# PATHOS_SOM_IO.net
KiCad netlist of a schematic drawn in Altium Designer
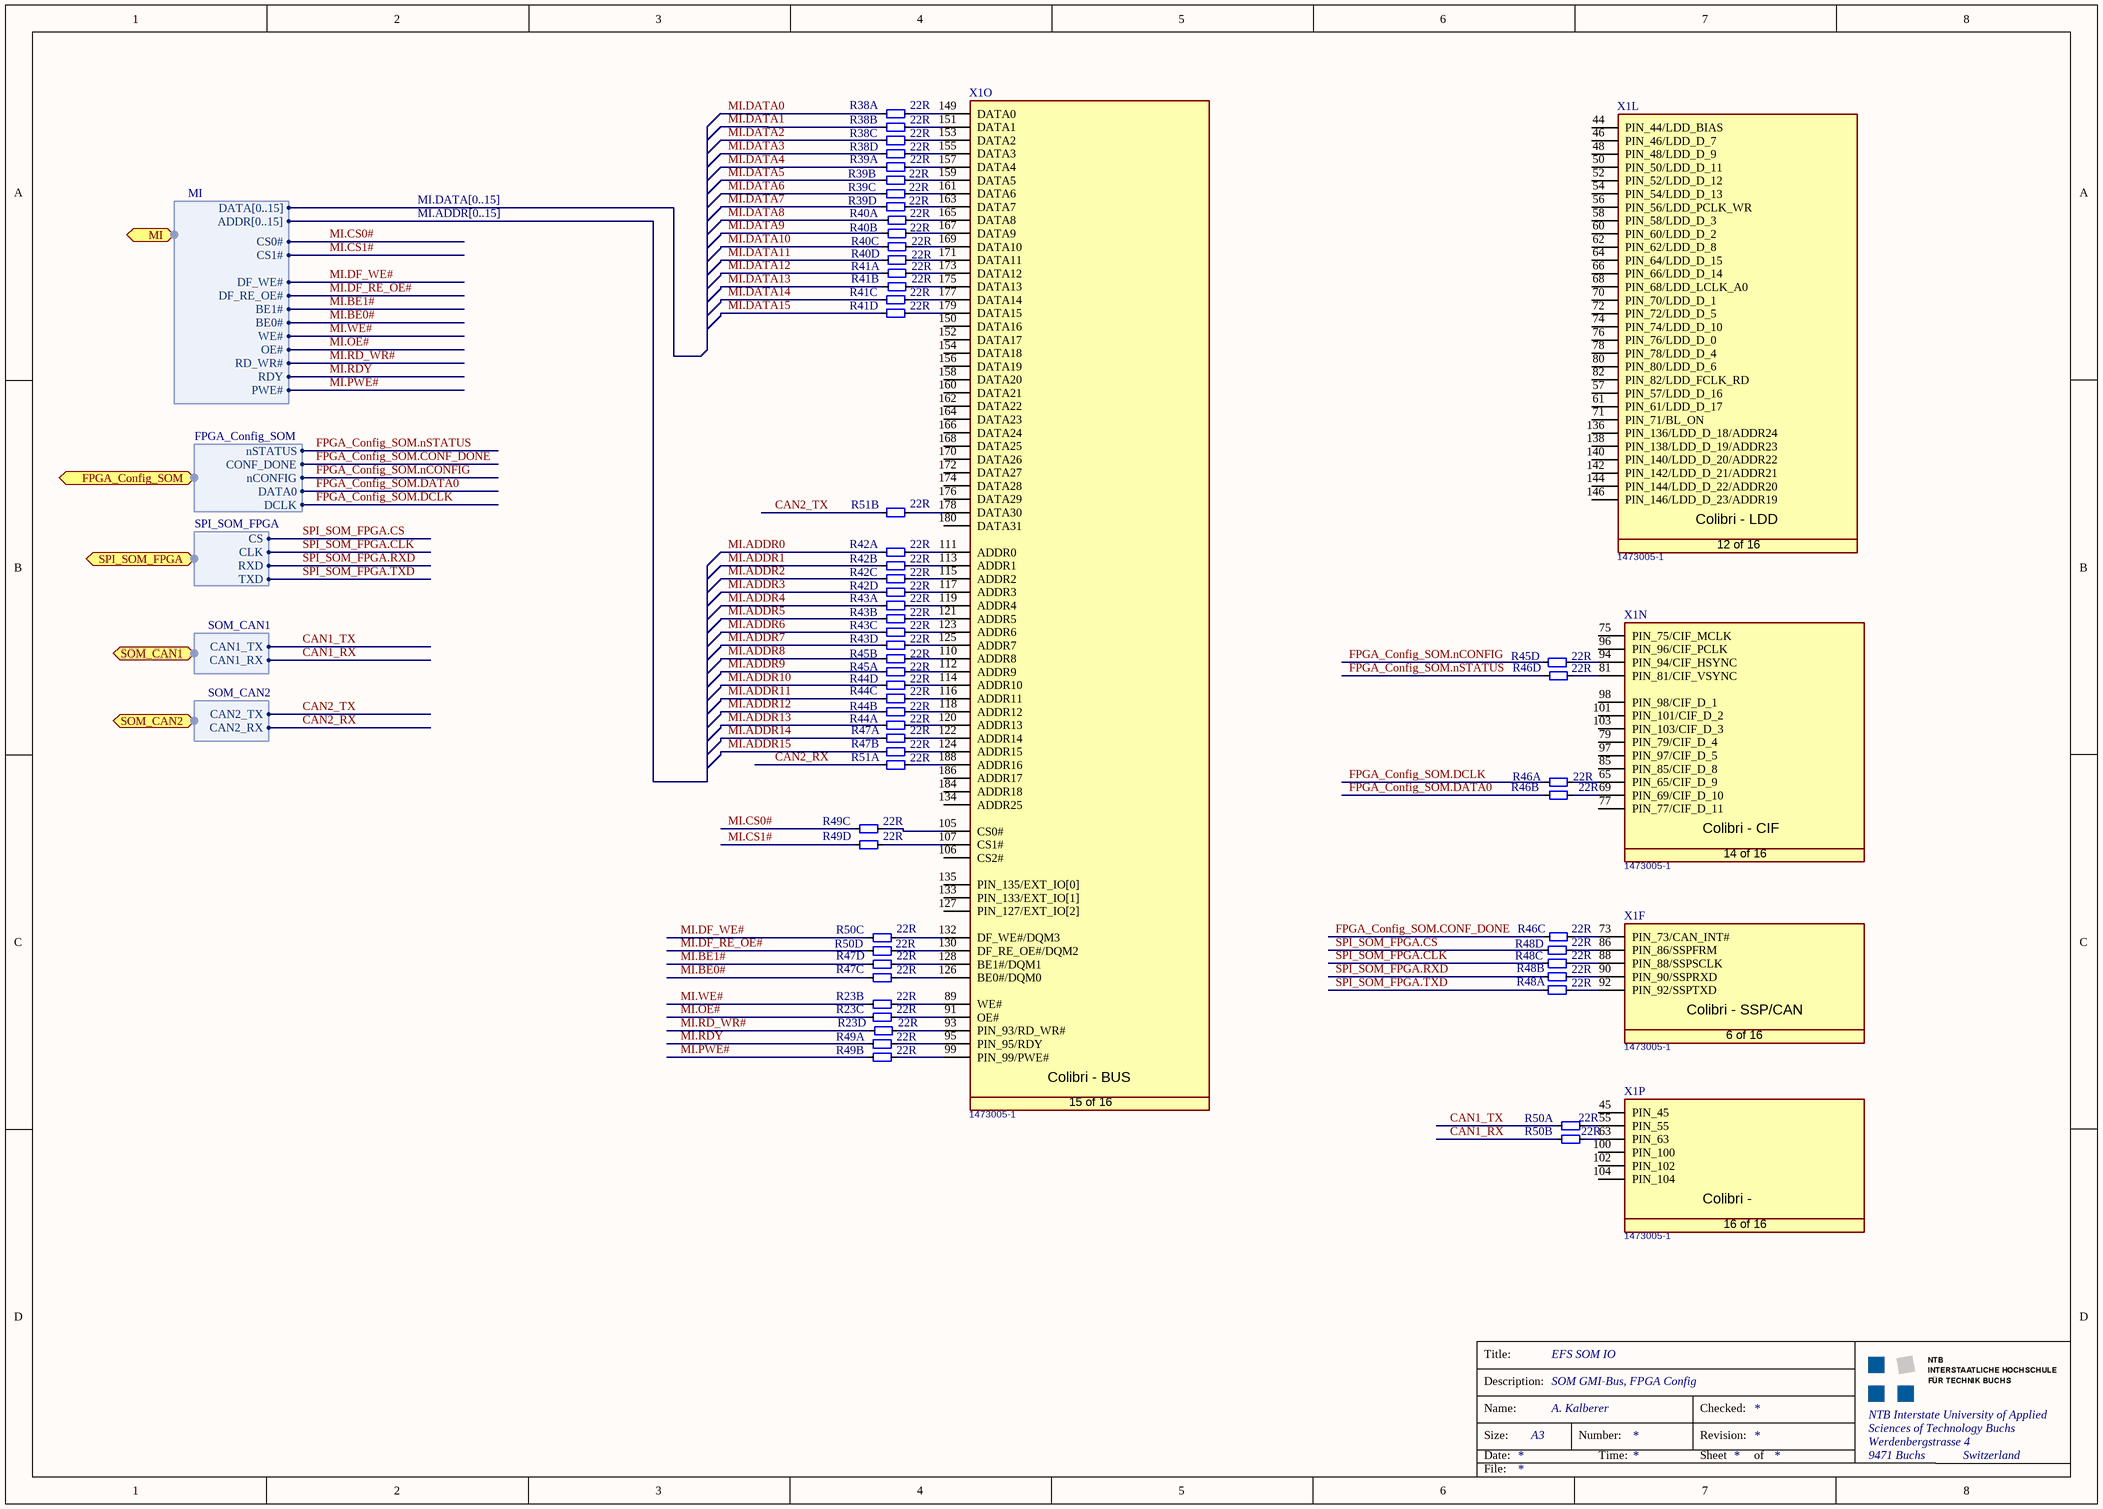
[diagram p0: PATHOS_SOM_IO.SchDoc]

(export (version "E")
  (design (tool "Eeschema 10.0.6"))
  (components
    (comp (ref "R23")
      (value "22R")
      (footprint "R_Array_CAT16-J4")
      (fields (field (name "Comment") "R Array"))
      (libsource (lib "EFSSensorboard_1") (part "R_Array"))
    )
    (comp (ref "R38")
      (value "22R")
      (footprint "R_Array_CAT16-J4")
      (fields (field (name "Comment") "R Array"))
      (libsource (lib "EFSSensorboard_1") (part "R_Array"))
    )
    (comp (ref "R39")
      (value "22R")
      (footprint "R_Array_CAT16-J4")
      (fields (field (name "Comment") "R Array"))
      (libsource (lib "EFSSensorboard_1") (part "R_Array"))
    )
    (comp (ref "R40")
      (value "22R")
      (footprint "R_Array_CAT16-J4")
      (fields (field (name "Comment") "R Array"))
      (libsource (lib "EFSSensorboard_1") (part "R_Array"))
    )
    (comp (ref "R41")
      (value "22R")
      (footprint "R_Array_CAT16-J4")
      (fields (field (name "Comment") "R Array"))
      (libsource (lib "EFSSensorboard_1") (part "R_Array"))
    )
    (comp (ref "R42")
      (value "22R")
      (footprint "R_Array_CAT16-J4")
      (fields (field (name "Comment") "R Array"))
      (libsource (lib "EFSSensorboard_1") (part "R_Array"))
    )
    (comp (ref "R43")
      (value "22R")
      (footprint "R_Array_CAT16-J4")
      (fields (field (name "Comment") "R Array"))
      (libsource (lib "EFSSensorboard_1") (part "R_Array"))
    )
    (comp (ref "R44")
      (value "22R")
      (footprint "R_Array_CAT16-J4")
      (fields (field (name "Comment") "R Array"))
      (libsource (lib "EFSSensorboard_1") (part "R_Array"))
    )
    (comp (ref "R45")
      (value "22R")
      (footprint "R_Array_CAT16-J4")
      (fields (field (name "Comment") "R Array"))
      (libsource (lib "EFSSensorboard_1") (part "R_Array"))
    )
    (comp (ref "R46")
      (value "22R")
      (footprint "R_Array_CAT16-J4")
      (fields (field (name "Comment") "R Array"))
      (libsource (lib "EFSSensorboard_1") (part "R_Array"))
    )
    (comp (ref "R47")
      (value "22R")
      (footprint "R_Array_CAT16-J4")
      (fields (field (name "Comment") "R Array"))
      (libsource (lib "EFS_Sensorboard") (part "R_Array"))
    )
    (comp (ref "R48")
      (value "22R")
      (footprint "R_Array_CAT16-J4")
      (fields (field (name "Comment") "R Array"))
      (libsource (lib "EFSSensorboard_1") (part "R_Array"))
    )
    (comp (ref "R49")
      (value "22R")
      (footprint "R_Array_CAT16-J4")
      (fields (field (name "Comment") "R Array"))
      (libsource (lib "EFSSensorboard_1") (part "R_Array"))
    )
    (comp (ref "R50")
      (value "22R")
      (footprint "R_Array_CAT16-J4")
      (fields (field (name "Comment") "R Array"))
      (libsource (lib "EFSSensorboard_1") (part "R_Array"))
    )
    (comp (ref "R51")
      (value "22R")
      (footprint "R_Array_CAT16-J4")
      (fields (field (name "Comment") "R Array"))
      (libsource (lib "EFS_Sensorboard") (part "R_Array"))
    )
    (comp (ref "X1")
      (value "CON-Tyco-1473005-1-200-0.6mm")
      (footprint "T_Tyco_1473005-1")
      (description "SODIMM Connector")
      (fields (field (name "MANUFACTURER PART NO.") "1473005-1"))
      (libsource (lib "EFS_Sensorboard") (part "CON-Tyco-1473005-1-200-0.6mm"))
    )
  )
  (nets
    (net (code "6") (name "/CAN1_RX") (class "Default")
      (node (ref "R50") (pin "2B") (pinfunction "2_2B") (pintype "passive"))
    )
    (net (code "7") (name "/CAN1_TX") (class "Default")
      (node (ref "R50") (pin "2A") (pinfunction "2_2A") (pintype "passive"))
    )
    (net (code "8") (name "/CAN2_RX") (class "Default")
      (node (ref "R51") (pin "1A") (pinfunction "1_1A") (pintype "passive"))
    )
    (net (code "9") (name "/CAN2_TX") (class "Default")
      (node (ref "R51") (pin "1B") (pinfunction "1_1B") (pintype "passive"))
    )
    (net (code "10") (name "/FPGA_Config_SOM.CONF_DONE") (class "Default")
      (node (ref "R46") (pin "1C") (pinfunction "1_1C") (pintype "passive"))
    )
    (net (code "11") (name "/FPGA_Config_SOM.DATA0") (class "Default")
      (node (ref "R46") (pin "1B") (pinfunction "1_1B") (pintype "passive"))
    )
    (net (code "12") (name "/FPGA_Config_SOM.DCLK") (class "Default")
      (node (ref "R46") (pin "1A") (pinfunction "1_1A") (pintype "passive"))
    )
    (net (code "13") (name "/FPGA_Config_SOM.nCONFIG") (class "Default")
      (node (ref "R45") (pin "1D") (pinfunction "1_1D") (pintype "passive"))
    )
    (net (code "14") (name "/FPGA_Config_SOM.nSTATUS") (class "Default")
      (node (ref "R46") (pin "1D") (pinfunction "1_1D") (pintype "passive"))
    )
    (net (code "15") (name "/MI.ADDR0") (class "Default")
      (node (ref "R42") (pin "1A") (pinfunction "1_1A") (pintype "passive"))
    )
    (net (code "16") (name "/MI.ADDR1") (class "Default")
      (node (ref "R42") (pin "1B") (pinfunction "1_1B") (pintype "passive"))
    )
    (net (code "17") (name "/MI.ADDR2") (class "Default")
      (node (ref "R42") (pin "1C") (pinfunction "1_1C") (pintype "passive"))
    )
    (net (code "18") (name "/MI.ADDR3") (class "Default")
      (node (ref "R42") (pin "1D") (pinfunction "1_1D") (pintype "passive"))
    )
    (net (code "19") (name "/MI.ADDR4") (class "Default")
      (node (ref "R43") (pin "1A") (pinfunction "1_1A") (pintype "passive"))
    )
    (net (code "20") (name "/MI.ADDR5") (class "Default")
      (node (ref "R43") (pin "1B") (pinfunction "1_1B") (pintype "passive"))
    )
    (net (code "21") (name "/MI.ADDR6") (class "Default")
      (node (ref "R43") (pin "1C") (pinfunction "1_1C") (pintype "passive"))
    )
    (net (code "22") (name "/MI.ADDR7") (class "Default")
      (node (ref "R43") (pin "1D") (pinfunction "1_1D") (pintype "passive"))
    )
    (net (code "23") (name "/MI.ADDR8") (class "Default")
      (node (ref "R45") (pin "1B") (pinfunction "1_1B") (pintype "passive"))
    )
    (net (code "24") (name "/MI.ADDR9") (class "Default")
      (node (ref "R45") (pin "1A") (pinfunction "1_1A") (pintype "passive"))
    )
    (net (code "25") (name "/MI.ADDR10") (class "Default")
      (node (ref "R44") (pin "1D") (pinfunction "1_1D") (pintype "passive"))
    )
    (net (code "26") (name "/MI.ADDR11") (class "Default")
      (node (ref "R44") (pin "1C") (pinfunction "1_1C") (pintype "passive"))
    )
    (net (code "27") (name "/MI.ADDR12") (class "Default")
      (node (ref "R44") (pin "1B") (pinfunction "1_1B") (pintype "passive"))
    )
    (net (code "28") (name "/MI.ADDR13") (class "Default")
      (node (ref "R44") (pin "1A") (pinfunction "1_1A") (pintype "passive"))
    )
    (net (code "29") (name "/MI.ADDR14") (class "Default")
      (node (ref "R47") (pin "1A") (pinfunction "1_1A") (pintype "passive"))
    )
    (net (code "30") (name "/MI.ADDR15") (class "Default")
      (node (ref "R47") (pin "1B") (pinfunction "1_1B") (pintype "passive"))
    )
    (net (code "32") (name "/MI.BE0#") (class "Default")
      (node (ref "R47") (pin "1C") (pinfunction "1_1C") (pintype "passive"))
    )
    (net (code "33") (name "/MI.BE1#") (class "Default")
      (node (ref "R47") (pin "1D") (pinfunction "1_1D") (pintype "passive"))
    )
    (net (code "34") (name "/MI.CS0#") (class "Default")
      (node (ref "R49") (pin "1C") (pinfunction "1_1C") (pintype "passive"))
    )
    (net (code "35") (name "/MI.CS1#") (class "Default")
      (node (ref "R49") (pin "1D") (pinfunction "1_1D") (pintype "passive"))
    )
    (net (code "36") (name "/MI.DATA0") (class "Default")
      (node (ref "R38") (pin "1A") (pinfunction "1_1A") (pintype "passive"))
    )
    (net (code "37") (name "/MI.DATA1") (class "Default")
      (node (ref "R38") (pin "1B") (pinfunction "1_1B") (pintype "passive"))
    )
    (net (code "38") (name "/MI.DATA2") (class "Default")
      (node (ref "R38") (pin "1C") (pinfunction "1_1C") (pintype "passive"))
    )
    (net (code "39") (name "/MI.DATA3") (class "Default")
      (node (ref "R38") (pin "1D") (pinfunction "1_1D") (pintype "passive"))
    )
    (net (code "40") (name "/MI.DATA4") (class "Default")
      (node (ref "R39") (pin "1A") (pinfunction "1_1A") (pintype "passive"))
    )
    (net (code "41") (name "/MI.DATA5") (class "Default")
      (node (ref "R39") (pin "1B") (pinfunction "1_1B") (pintype "passive"))
    )
    (net (code "42") (name "/MI.DATA6") (class "Default")
      (node (ref "R39") (pin "1C") (pinfunction "1_1C") (pintype "passive"))
    )
    (net (code "43") (name "/MI.DATA7") (class "Default")
      (node (ref "R39") (pin "1D") (pinfunction "1_1D") (pintype "passive"))
    )
    (net (code "44") (name "/MI.DATA8") (class "Default")
      (node (ref "R40") (pin "1A") (pinfunction "1_1A") (pintype "passive"))
    )
    (net (code "45") (name "/MI.DATA9") (class "Default")
      (node (ref "R40") (pin "1B") (pinfunction "1_1B") (pintype "passive"))
    )
    (net (code "46") (name "/MI.DATA10") (class "Default")
      (node (ref "R40") (pin "1C") (pinfunction "1_1C") (pintype "passive"))
    )
    (net (code "47") (name "/MI.DATA11") (class "Default")
      (node (ref "R40") (pin "1D") (pinfunction "1_1D") (pintype "passive"))
    )
    (net (code "48") (name "/MI.DATA12") (class "Default")
      (node (ref "R41") (pin "1A") (pinfunction "1_1A") (pintype "passive"))
    )
    (net (code "49") (name "/MI.DATA13") (class "Default")
      (node (ref "R41") (pin "1B") (pinfunction "1_1B") (pintype "passive"))
    )
    (net (code "50") (name "/MI.DATA14") (class "Default")
      (node (ref "R41") (pin "1C") (pinfunction "1_1C") (pintype "passive"))
    )
    (net (code "51") (name "/MI.DATA15") (class "Default")
      (node (ref "R41") (pin "1D") (pinfunction "1_1D") (pintype "passive"))
    )
    (net (code "52") (name "/MI.DF_RE_OE#") (class "Default")
      (node (ref "R50") (pin "1D") (pinfunction "1_1D") (pintype "passive"))
    )
    (net (code "53") (name "/MI.DF_WE#") (class "Default")
      (node (ref "R50") (pin "1C") (pinfunction "1_1C") (pintype "passive"))
    )
    (net (code "54") (name "/MI.OE#") (class "Default")
      (node (ref "R23") (pin "1C") (pinfunction "1_1C") (pintype "passive"))
    )
    (net (code "55") (name "/MI.PWE#") (class "Default")
      (node (ref "R49") (pin "1B") (pinfunction "1_1B") (pintype "passive"))
    )
    (net (code "56") (name "/MI.RDY") (class "Default")
      (node (ref "R49") (pin "1A") (pinfunction "1_1A") (pintype "passive"))
    )
    (net (code "57") (name "/MI.RD_WR#") (class "Default")
      (node (ref "R23") (pin "1D") (pinfunction "1_1D") (pintype "passive"))
    )
    (net (code "58") (name "/MI.WE#") (class "Default")
      (node (ref "R23") (pin "1B") (pinfunction "1_1B") (pintype "passive"))
    )
    (net (code "60") (name "/SPI_SOM_FPGA.CLK") (class "Default")
      (node (ref "R48") (pin "1C") (pinfunction "1_1C") (pintype "passive"))
    )
    (net (code "61") (name "/SPI_SOM_FPGA.CS") (class "Default")
      (node (ref "R48") (pin "1D") (pinfunction "1_1D") (pintype "passive"))
    )
    (net (code "62") (name "/SPI_SOM_FPGA.RXD") (class "Default")
      (node (ref "R48") (pin "1B") (pinfunction "1_1B") (pintype "passive"))
    )
    (net (code "63") (name "/SPI_SOM_FPGA.TXD") (class "Default")
      (node (ref "R48") (pin "1A") (pinfunction "1_1A") (pintype "passive"))
    )
    (net (code "69") (name "Net-(R23B-2)") (class "Default")
      (node (ref "R23") (pin "2B") (pinfunction "2_2B") (pintype "passive"))
      (node (ref "X1") (pin "89") (pinfunction "WE#_89") (pintype "passive"))
    )
    (net (code "70") (name "Net-(R23C-2)") (class "Default")
      (node (ref "R23") (pin "2C") (pinfunction "2_2C") (pintype "passive"))
      (node (ref "X1") (pin "91") (pinfunction "OE#_91") (pintype "passive"))
    )
    (net (code "71") (name "Net-(R23D-2)") (class "Default")
      (node (ref "R23") (pin "2D") (pinfunction "2_2D") (pintype "passive"))
      (node (ref "X1") (pin "93") (pinfunction "PIN_93/RD_WR#_93") (pintype "passive"))
    )
    (net (code "72") (name "Net-(R38A-2)") (class "Default")
      (node (ref "R38") (pin "2A") (pinfunction "2_2A") (pintype "passive"))
      (node (ref "X1") (pin "149") (pinfunction "DATA0_149") (pintype "passive"))
    )
    (net (code "73") (name "Net-(R38B-2)") (class "Default")
      (node (ref "R38") (pin "2B") (pinfunction "2_2B") (pintype "passive"))
      (node (ref "X1") (pin "151") (pinfunction "DATA1_151") (pintype "passive"))
    )
    (net (code "74") (name "Net-(R38C-2)") (class "Default")
      (node (ref "R38") (pin "2C") (pinfunction "2_2C") (pintype "passive"))
      (node (ref "X1") (pin "153") (pinfunction "DATA2_153") (pintype "passive"))
    )
    (net (code "75") (name "Net-(R38D-2)") (class "Default")
      (node (ref "R38") (pin "2D") (pinfunction "2_2D") (pintype "passive"))
      (node (ref "X1") (pin "155") (pinfunction "DATA3_155") (pintype "passive"))
    )
    (net (code "76") (name "Net-(R39A-2)") (class "Default")
      (node (ref "R39") (pin "2A") (pinfunction "2_2A") (pintype "passive"))
      (node (ref "X1") (pin "157") (pinfunction "DATA4_157") (pintype "passive"))
    )
    (net (code "77") (name "Net-(R39B-2)") (class "Default")
      (node (ref "R39") (pin "2B") (pinfunction "2_2B") (pintype "passive"))
      (node (ref "X1") (pin "159") (pinfunction "DATA5_159") (pintype "passive"))
    )
    (net (code "78") (name "Net-(R39C-2)") (class "Default")
      (node (ref "R39") (pin "2C") (pinfunction "2_2C") (pintype "passive"))
      (node (ref "X1") (pin "161") (pinfunction "DATA6_161") (pintype "passive"))
    )
    (net (code "79") (name "Net-(R39D-2)") (class "Default")
      (node (ref "R39") (pin "2D") (pinfunction "2_2D") (pintype "passive"))
      (node (ref "X1") (pin "163") (pinfunction "DATA7_163") (pintype "passive"))
    )
    (net (code "80") (name "Net-(R40A-2)") (class "Default")
      (node (ref "R40") (pin "2A") (pinfunction "2_2A") (pintype "passive"))
      (node (ref "X1") (pin "165") (pinfunction "DATA8_165") (pintype "passive"))
    )
    (net (code "81") (name "Net-(R40B-2)") (class "Default")
      (node (ref "R40") (pin "2B") (pinfunction "2_2B") (pintype "passive"))
      (node (ref "X1") (pin "167") (pinfunction "DATA9_167") (pintype "passive"))
    )
    (net (code "82") (name "Net-(R40C-2)") (class "Default")
      (node (ref "R40") (pin "2C") (pinfunction "2_2C") (pintype "passive"))
      (node (ref "X1") (pin "169") (pinfunction "DATA10_169") (pintype "passive"))
    )
    (net (code "83") (name "Net-(R40D-2)") (class "Default")
      (node (ref "R40") (pin "2D") (pinfunction "2_2D") (pintype "passive"))
      (node (ref "X1") (pin "171") (pinfunction "DATA11_171") (pintype "passive"))
    )
    (net (code "84") (name "Net-(R41A-2)") (class "Default")
      (node (ref "R41") (pin "2A") (pinfunction "2_2A") (pintype "passive"))
      (node (ref "X1") (pin "173") (pinfunction "DATA12_173") (pintype "passive"))
    )
    (net (code "85") (name "Net-(R41B-2)") (class "Default")
      (node (ref "R41") (pin "2B") (pinfunction "2_2B") (pintype "passive"))
      (node (ref "X1") (pin "175") (pinfunction "DATA13_175") (pintype "passive"))
    )
    (net (code "86") (name "Net-(R41C-2)") (class "Default")
      (node (ref "R41") (pin "2C") (pinfunction "2_2C") (pintype "passive"))
      (node (ref "X1") (pin "177") (pinfunction "DATA14_177") (pintype "passive"))
    )
    (net (code "87") (name "Net-(R41D-2)") (class "Default")
      (node (ref "R41") (pin "2D") (pinfunction "2_2D") (pintype "passive"))
      (node (ref "X1") (pin "179") (pinfunction "DATA15_179") (pintype "passive"))
    )
    (net (code "88") (name "Net-(R42A-2)") (class "Default")
      (node (ref "R42") (pin "2A") (pinfunction "2_2A") (pintype "passive"))
      (node (ref "X1") (pin "111") (pinfunction "ADDR0_111") (pintype "passive"))
    )
    (net (code "89") (name "Net-(R42B-2)") (class "Default")
      (node (ref "R42") (pin "2B") (pinfunction "2_2B") (pintype "passive"))
      (node (ref "X1") (pin "113") (pinfunction "ADDR1_113") (pintype "passive"))
    )
    (net (code "90") (name "Net-(R42C-2)") (class "Default")
      (node (ref "R42") (pin "2C") (pinfunction "2_2C") (pintype "passive"))
      (node (ref "X1") (pin "115") (pinfunction "ADDR2_115") (pintype "passive"))
    )
    (net (code "91") (name "Net-(R42D-2)") (class "Default")
      (node (ref "R42") (pin "2D") (pinfunction "2_2D") (pintype "passive"))
      (node (ref "X1") (pin "117") (pinfunction "ADDR3_117") (pintype "passive"))
    )
    (net (code "92") (name "Net-(R43A-2)") (class "Default")
      (node (ref "R43") (pin "2A") (pinfunction "2_2A") (pintype "passive"))
      (node (ref "X1") (pin "119") (pinfunction "ADDR4_119") (pintype "passive"))
    )
    (net (code "93") (name "Net-(R43B-2)") (class "Default")
      (node (ref "R43") (pin "2B") (pinfunction "2_2B") (pintype "passive"))
      (node (ref "X1") (pin "121") (pinfunction "ADDR5_121") (pintype "passive"))
    )
    (net (code "94") (name "Net-(R43C-2)") (class "Default")
      (node (ref "R43") (pin "2C") (pinfunction "2_2C") (pintype "passive"))
      (node (ref "X1") (pin "123") (pinfunction "ADDR6_123") (pintype "passive"))
    )
    (net (code "95") (name "Net-(R43D-2)") (class "Default")
      (node (ref "R43") (pin "2D") (pinfunction "2_2D") (pintype "passive"))
      (node (ref "X1") (pin "125") (pinfunction "ADDR7_125") (pintype "passive"))
    )
    (net (code "96") (name "Net-(R44A-2)") (class "Default")
      (node (ref "R44") (pin "2A") (pinfunction "2_2A") (pintype "passive"))
      (node (ref "X1") (pin "120") (pinfunction "ADDR13_120") (pintype "passive"))
    )
    (net (code "97") (name "Net-(R44B-2)") (class "Default")
      (node (ref "R44") (pin "2B") (pinfunction "2_2B") (pintype "passive"))
      (node (ref "X1") (pin "118") (pinfunction "ADDR12_118") (pintype "passive"))
    )
    (net (code "98") (name "Net-(R44C-2)") (class "Default")
      (node (ref "R44") (pin "2C") (pinfunction "2_2C") (pintype "passive"))
      (node (ref "X1") (pin "116") (pinfunction "ADDR11_116") (pintype "passive"))
    )
    (net (code "99") (name "Net-(R44D-2)") (class "Default")
      (node (ref "R44") (pin "2D") (pinfunction "2_2D") (pintype "passive"))
      (node (ref "X1") (pin "114") (pinfunction "ADDR10_114") (pintype "passive"))
    )
    (net (code "100") (name "Net-(R45A-2)") (class "Default")
      (node (ref "R45") (pin "2A") (pinfunction "2_2A") (pintype "passive"))
      (node (ref "X1") (pin "112") (pinfunction "ADDR9_112") (pintype "passive"))
    )
    (net (code "101") (name "Net-(R45B-2)") (class "Default")
      (node (ref "R45") (pin "2B") (pinfunction "2_2B") (pintype "passive"))
      (node (ref "X1") (pin "110") (pinfunction "ADDR8_110") (pintype "passive"))
    )
    (net (code "102") (name "Net-(R45D-2)") (class "Default")
      (node (ref "R45") (pin "2D") (pinfunction "2_2D") (pintype "passive"))
      (node (ref "X1") (pin "94") (pinfunction "PIN_94/CIF_HSYNC_94") (pintype "passive"))
    )
    (net (code "103") (name "Net-(R46A-2)") (class "Default")
      (node (ref "R46") (pin "2A") (pinfunction "2_2A") (pintype "passive"))
      (node (ref "X1") (pin "65") (pinfunction "PIN_65/CIF_D_9_65") (pintype "passive"))
    )
    (net (code "104") (name "Net-(R46B-2)") (class "Default")
      (node (ref "R46") (pin "2B") (pinfunction "2_2B") (pintype "passive"))
      (node (ref "X1") (pin "69") (pinfunction "PIN_69/CIF_D_10_69") (pintype "passive"))
    )
    (net (code "105") (name "Net-(R46C-2)") (class "Default")
      (node (ref "R46") (pin "2C") (pinfunction "2_2C") (pintype "passive"))
      (node (ref "X1") (pin "73") (pinfunction "PIN_73/CAN_INT#_73") (pintype "passive"))
    )
    (net (code "106") (name "Net-(R46D-2)") (class "Default")
      (node (ref "R46") (pin "2D") (pinfunction "2_2D") (pintype "passive"))
      (node (ref "X1") (pin "81") (pinfunction "PIN_81/CIF_VSYNC_81") (pintype "passive"))
    )
    (net (code "107") (name "Net-(R47A-2)") (class "Default")
      (node (ref "R47") (pin "2A") (pinfunction "2_2A") (pintype "passive"))
      (node (ref "X1") (pin "122") (pinfunction "ADDR14_122") (pintype "passive"))
    )
    (net (code "108") (name "Net-(R47B-2)") (class "Default")
      (node (ref "R47") (pin "2B") (pinfunction "2_2B") (pintype "passive"))
      (node (ref "X1") (pin "124") (pinfunction "ADDR15_124") (pintype "passive"))
    )
    (net (code "109") (name "Net-(R47C-2)") (class "Default")
      (node (ref "R47") (pin "2C") (pinfunction "2_2C") (pintype "passive"))
      (node (ref "X1") (pin "126") (pinfunction "BE0#/DQM0_126") (pintype "passive"))
    )
    (net (code "110") (name "Net-(R47D-2)") (class "Default")
      (node (ref "R47") (pin "2D") (pinfunction "2_2D") (pintype "passive"))
      (node (ref "X1") (pin "128") (pinfunction "BE1#/DQM1_128") (pintype "passive"))
    )
    (net (code "111") (name "Net-(R48A-2)") (class "Default")
      (node (ref "R48") (pin "2A") (pinfunction "2_2A") (pintype "passive"))
      (node (ref "X1") (pin "92") (pinfunction "PIN_92/SSPTXD_92") (pintype "passive"))
    )
    (net (code "112") (name "Net-(R48B-2)") (class "Default")
      (node (ref "R48") (pin "2B") (pinfunction "2_2B") (pintype "passive"))
      (node (ref "X1") (pin "90") (pinfunction "PIN_90/SSPRXD_90") (pintype "passive"))
    )
    (net (code "113") (name "Net-(R48C-2)") (class "Default")
      (node (ref "R48") (pin "2C") (pinfunction "2_2C") (pintype "passive"))
      (node (ref "X1") (pin "88") (pinfunction "PIN_88/SSPSCLK_88") (pintype "passive"))
    )
    (net (code "114") (name "Net-(R48D-2)") (class "Default")
      (node (ref "R48") (pin "2D") (pinfunction "2_2D") (pintype "passive"))
      (node (ref "X1") (pin "86") (pinfunction "PIN_86/SSPFRM_86") (pintype "passive"))
    )
    (net (code "115") (name "Net-(R49A-2)") (class "Default")
      (node (ref "R49") (pin "2A") (pinfunction "2_2A") (pintype "passive"))
      (node (ref "X1") (pin "95") (pinfunction "PIN_95/RDY_95") (pintype "passive"))
    )
    (net (code "116") (name "Net-(R49B-2)") (class "Default")
      (node (ref "R49") (pin "2B") (pinfunction "2_2B") (pintype "passive"))
      (node (ref "X1") (pin "99") (pinfunction "PIN_99/PWE#_99") (pintype "passive"))
    )
    (net (code "117") (name "Net-(R49C-2)") (class "Default")
      (node (ref "R49") (pin "2C") (pinfunction "2_2C") (pintype "passive"))
      (node (ref "X1") (pin "105") (pinfunction "CS0#_105") (pintype "passive"))
    )
    (net (code "118") (name "Net-(R49D-2)") (class "Default")
      (node (ref "R49") (pin "2D") (pinfunction "2_2D") (pintype "passive"))
      (node (ref "X1") (pin "107") (pinfunction "CS1#_107") (pintype "passive"))
    )
    (net (code "119") (name "Net-(R50A-1)") (class "Default")
      (node (ref "R50") (pin "1A") (pinfunction "1_1A") (pintype "passive"))
      (node (ref "X1") (pin "55") (pinfunction "PIN_55_55") (pintype "passive"))
    )
    (net (code "120") (name "Net-(R50B-1)") (class "Default")
      (node (ref "R50") (pin "1B") (pinfunction "1_1B") (pintype "passive"))
      (node (ref "X1") (pin "63") (pinfunction "PIN_63_63") (pintype "passive"))
    )
    (net (code "121") (name "Net-(R50C-2)") (class "Default")
      (node (ref "R50") (pin "2C") (pinfunction "2_2C") (pintype "passive"))
      (node (ref "X1") (pin "132") (pinfunction "DF_WE#/DQM3_132") (pintype "passive"))
    )
    (net (code "122") (name "Net-(R50D-2)") (class "Default")
      (node (ref "R50") (pin "2D") (pinfunction "2_2D") (pintype "passive"))
      (node (ref "X1") (pin "130") (pinfunction "DF_RE_OE#/DQM2_130") (pintype "passive"))
    )
    (net (code "123") (name "Net-(R51A-2)") (class "Default")
      (node (ref "R51") (pin "2A") (pinfunction "2_2A") (pintype "passive"))
      (node (ref "X1") (pin "188") (pinfunction "ADDR16_188") (pintype "passive"))
    )
    (net (code "124") (name "Net-(R51B-2)") (class "Default")
      (node (ref "R51") (pin "2B") (pinfunction "2_2B") (pintype "passive"))
      (node (ref "X1") (pin "178") (pinfunction "DATA30_178") (pintype "passive"))
    )
    (net (code "125") (name "unconnected-(X1L-PIN_44{slash}LDD_BIAS-Pad44)") (class "Default")
      (node (ref "X1") (pin "44") (pinfunction "PIN_44/LDD_BIAS_44") (pintype "passive"))
    )
    (net (code "126") (name "unconnected-(X1L-PIN_46{slash}LDD_D_7-Pad46)") (class "Default")
      (node (ref "X1") (pin "46") (pinfunction "PIN_46/LDD_D_7_46") (pintype "passive"))
    )
    (net (code "127") (name "unconnected-(X1L-PIN_48{slash}LDD_D_9-Pad48)") (class "Default")
      (node (ref "X1") (pin "48") (pinfunction "PIN_48/LDD_D_9_48") (pintype "passive"))
    )
    (net (code "128") (name "unconnected-(X1L-PIN_50{slash}LDD_D_11-Pad50)") (class "Default")
      (node (ref "X1") (pin "50") (pinfunction "PIN_50/LDD_D_11_50") (pintype "passive"))
    )
    (net (code "129") (name "unconnected-(X1L-PIN_52{slash}LDD_D_12-Pad52)") (class "Default")
      (node (ref "X1") (pin "52") (pinfunction "PIN_52/LDD_D_12_52") (pintype "passive"))
    )
    (net (code "130") (name "unconnected-(X1L-PIN_54{slash}LDD_D_13-Pad54)") (class "Default")
      (node (ref "X1") (pin "54") (pinfunction "PIN_54/LDD_D_13_54") (pintype "passive"))
    )
    (net (code "131") (name "unconnected-(X1L-PIN_56{slash}LDD_PCLK_WR-Pad56)") (class "Default")
      (node (ref "X1") (pin "56") (pinfunction "PIN_56/LDD_PCLK_WR_56") (pintype "passive"))
    )
    (net (code "132") (name "unconnected-(X1L-PIN_57{slash}LDD_D_16-Pad57)") (class "Default")
      (node (ref "X1") (pin "57") (pinfunction "PIN_57/LDD_D_16_57") (pintype "passive"))
    )
    (net (code "133") (name "unconnected-(X1L-PIN_58{slash}LDD_D_3-Pad58)") (class "Default")
      (node (ref "X1") (pin "58") (pinfunction "PIN_58/LDD_D_3_58") (pintype "passive"))
    )
    (net (code "134") (name "unconnected-(X1L-PIN_60{slash}LDD_D_2-Pad60)") (class "Default")
      (node (ref "X1") (pin "60") (pinfunction "PIN_60/LDD_D_2_60") (pintype "passive"))
    )
    (net (code "135") (name "unconnected-(X1L-PIN_61{slash}LDD_D_17-Pad61)") (class "Default")
      (node (ref "X1") (pin "61") (pinfunction "PIN_61/LDD_D_17_61") (pintype "passive"))
    )
    (net (code "136") (name "unconnected-(X1L-PIN_62{slash}LDD_D_8-Pad62)") (class "Default")
      (node (ref "X1") (pin "62") (pinfunction "PIN_62/LDD_D_8_62") (pintype "passive"))
    )
    (net (code "137") (name "unconnected-(X1L-PIN_64{slash}LDD_D_15-Pad64)") (class "Default")
      (node (ref "X1") (pin "64") (pinfunction "PIN_64/LDD_D_15_64") (pintype "passive"))
    )
    (net (code "138") (name "unconnected-(X1L-PIN_66{slash}LDD_D_14-Pad66)") (class "Default")
      (node (ref "X1") (pin "66") (pinfunction "PIN_66/LDD_D_14_66") (pintype "passive"))
    )
    (net (code "139") (name "unconnected-(X1L-PIN_68{slash}LDD_LCLK_A0-Pad68)") (class "Default")
      (node (ref "X1") (pin "68") (pinfunction "PIN_68/LDD_LCLK_A0_68") (pintype "passive"))
    )
    (net (code "140") (name "unconnected-(X1L-PIN_70{slash}LDD_D_1-Pad70)") (class "Default")
      (node (ref "X1") (pin "70") (pinfunction "PIN_70/LDD_D_1_70") (pintype "passive"))
    )
    (net (code "141") (name "unconnected-(X1L-PIN_71{slash}BL_ON-Pad71)") (class "Default")
      (node (ref "X1") (pin "71") (pinfunction "PIN_71/BL_ON_71") (pintype "passive"))
    )
    (net (code "142") (name "unconnected-(X1L-PIN_72{slash}LDD_D_5-Pad72)") (class "Default")
      (node (ref "X1") (pin "72") (pinfunction "PIN_72/LDD_D_5_72") (pintype "passive"))
    )
    (net (code "143") (name "unconnected-(X1L-PIN_74{slash}LDD_D_10-Pad74)") (class "Default")
      (node (ref "X1") (pin "74") (pinfunction "PIN_74/LDD_D_10_74") (pintype "passive"))
    )
    (net (code "144") (name "unconnected-(X1L-PIN_76{slash}LDD_D_0-Pad76)") (class "Default")
      (node (ref "X1") (pin "76") (pinfunction "PIN_76/LDD_D_0_76") (pintype "passive"))
    )
    (net (code "145") (name "unconnected-(X1L-PIN_78{slash}LDD_D_4-Pad78)") (class "Default")
      (node (ref "X1") (pin "78") (pinfunction "PIN_78/LDD_D_4_78") (pintype "passive"))
    )
    (net (code "146") (name "unconnected-(X1L-PIN_80{slash}LDD_D_6-Pad80)") (class "Default")
      (node (ref "X1") (pin "80") (pinfunction "PIN_80/LDD_D_6_80") (pintype "passive"))
    )
    (net (code "147") (name "unconnected-(X1L-PIN_82{slash}LDD_FCLK_RD-Pad82)") (class "Default")
      (node (ref "X1") (pin "82") (pinfunction "PIN_82/LDD_FCLK_RD_82") (pintype "passive"))
    )
    (net (code "148") (name "unconnected-(X1L-PIN_136{slash}LDD_D_18{slash}ADDR24-Pad136)") (class "Default")
      (node (ref "X1") (pin "136") (pinfunction "PIN_136/LDD_D_18/ADDR24_136") (pintype "passive"))
    )
    (net (code "149") (name "unconnected-(X1L-PIN_138{slash}LDD_D_19{slash}ADDR23-Pad138)") (class "Default")
      (node (ref "X1") (pin "138") (pinfunction "PIN_138/LDD_D_19/ADDR23_138") (pintype "passive"))
    )
    (net (code "150") (name "unconnected-(X1L-PIN_140{slash}LDD_D_20{slash}ADDR22-Pad140)") (class "Default")
      (node (ref "X1") (pin "140") (pinfunction "PIN_140/LDD_D_20/ADDR22_140") (pintype "passive"))
    )
    (net (code "151") (name "unconnected-(X1L-PIN_142{slash}LDD_D_21{slash}ADDR21-Pad142)") (class "Default")
      (node (ref "X1") (pin "142") (pinfunction "PIN_142/LDD_D_21/ADDR21_142") (pintype "passive"))
    )
    (net (code "152") (name "unconnected-(X1L-PIN_144{slash}LDD_D_22{slash}ADDR20-Pad144)") (class "Default")
      (node (ref "X1") (pin "144") (pinfunction "PIN_144/LDD_D_22/ADDR20_144") (pintype "passive"))
    )
    (net (code "153") (name "unconnected-(X1L-PIN_146{slash}LDD_D_23{slash}ADDR19-Pad146)") (class "Default")
      (node (ref "X1") (pin "146") (pinfunction "PIN_146/LDD_D_23/ADDR19_146") (pintype "passive"))
    )
    (net (code "154") (name "unconnected-(X1N-PIN_75{slash}CIF_MCLK-Pad75)") (class "Default")
      (node (ref "X1") (pin "75") (pinfunction "PIN_75/CIF_MCLK_75") (pintype "passive"))
    )
    (net (code "155") (name "unconnected-(X1N-PIN_77{slash}CIF_D_11-Pad77)") (class "Default")
      (node (ref "X1") (pin "77") (pinfunction "PIN_77/CIF_D_11_77") (pintype "passive"))
    )
    (net (code "156") (name "unconnected-(X1N-PIN_79{slash}CIF_D_4-Pad79)") (class "Default")
      (node (ref "X1") (pin "79") (pinfunction "PIN_79/CIF_D_4_79") (pintype "passive"))
    )
    (net (code "157") (name "unconnected-(X1N-PIN_85{slash}CIF_D_8-Pad85)") (class "Default")
      (node (ref "X1") (pin "85") (pinfunction "PIN_85/CIF_D_8_85") (pintype "passive"))
    )
    (net (code "158") (name "unconnected-(X1N-PIN_96{slash}CIF_PCLK-Pad96)") (class "Default")
      (node (ref "X1") (pin "96") (pinfunction "PIN_96/CIF_PCLK_96") (pintype "passive"))
    )
    (net (code "159") (name "unconnected-(X1N-PIN_97{slash}CIF_D_5-Pad97)") (class "Default")
      (node (ref "X1") (pin "97") (pinfunction "PIN_97/CIF_D_5_97") (pintype "passive"))
    )
    (net (code "160") (name "unconnected-(X1N-PIN_98{slash}CIF_D_1-Pad98)") (class "Default")
      (node (ref "X1") (pin "98") (pinfunction "PIN_98/CIF_D_1_98") (pintype "passive"))
    )
    (net (code "161") (name "unconnected-(X1N-PIN_101{slash}CIF_D_2-Pad101)") (class "Default")
      (node (ref "X1") (pin "101") (pinfunction "PIN_101/CIF_D_2_101") (pintype "passive"))
    )
    (net (code "162") (name "unconnected-(X1N-PIN_103{slash}CIF_D_3-Pad103)") (class "Default")
      (node (ref "X1") (pin "103") (pinfunction "PIN_103/CIF_D_3_103") (pintype "passive"))
    )
    (net (code "163") (name "unconnected-(X1O-ADDR17-Pad186)") (class "Default")
      (node (ref "X1") (pin "186") (pinfunction "ADDR17_186") (pintype "passive"))
    )
    (net (code "164") (name "unconnected-(X1O-ADDR18-Pad184)") (class "Default")
      (node (ref "X1") (pin "184") (pinfunction "ADDR18_184") (pintype "passive"))
    )
    (net (code "165") (name "unconnected-(X1O-ADDR25-Pad134)") (class "Default")
      (node (ref "X1") (pin "134") (pinfunction "ADDR25_134") (pintype "passive"))
    )
    (net (code "166") (name "unconnected-(X1O-CS2#-Pad106)") (class "Default")
      (node (ref "X1") (pin "106") (pinfunction "CS2#_106") (pintype "passive"))
    )
    (net (code "167") (name "unconnected-(X1O-DATA16-Pad150)") (class "Default")
      (node (ref "X1") (pin "150") (pinfunction "DATA16_150") (pintype "passive"))
    )
    (net (code "168") (name "unconnected-(X1O-DATA17-Pad152)") (class "Default")
      (node (ref "X1") (pin "152") (pinfunction "DATA17_152") (pintype "passive"))
    )
    (net (code "169") (name "unconnected-(X1O-DATA18-Pad154)") (class "Default")
      (node (ref "X1") (pin "154") (pinfunction "DATA18_154") (pintype "passive"))
    )
    (net (code "170") (name "unconnected-(X1O-DATA19-Pad156)") (class "Default")
      (node (ref "X1") (pin "156") (pinfunction "DATA19_156") (pintype "passive"))
    )
    (net (code "171") (name "unconnected-(X1O-DATA20-Pad158)") (class "Default")
      (node (ref "X1") (pin "158") (pinfunction "DATA20_158") (pintype "passive"))
    )
    (net (code "172") (name "unconnected-(X1O-DATA21-Pad160)") (class "Default")
      (node (ref "X1") (pin "160") (pinfunction "DATA21_160") (pintype "passive"))
    )
    (net (code "173") (name "unconnected-(X1O-DATA22-Pad162)") (class "Default")
      (node (ref "X1") (pin "162") (pinfunction "DATA22_162") (pintype "passive"))
    )
    (net (code "174") (name "unconnected-(X1O-DATA23-Pad164)") (class "Default")
      (node (ref "X1") (pin "164") (pinfunction "DATA23_164") (pintype "passive"))
    )
    (net (code "175") (name "unconnected-(X1O-DATA24-Pad166)") (class "Default")
      (node (ref "X1") (pin "166") (pinfunction "DATA24_166") (pintype "passive"))
    )
    (net (code "176") (name "unconnected-(X1O-DATA25-Pad168)") (class "Default")
      (node (ref "X1") (pin "168") (pinfunction "DATA25_168") (pintype "passive"))
    )
    (net (code "177") (name "unconnected-(X1O-DATA26-Pad170)") (class "Default")
      (node (ref "X1") (pin "170") (pinfunction "DATA26_170") (pintype "passive"))
    )
    (net (code "178") (name "unconnected-(X1O-DATA27-Pad172)") (class "Default")
      (node (ref "X1") (pin "172") (pinfunction "DATA27_172") (pintype "passive"))
    )
    (net (code "179") (name "unconnected-(X1O-DATA28-Pad174)") (class "Default")
      (node (ref "X1") (pin "174") (pinfunction "DATA28_174") (pintype "passive"))
    )
    (net (code "180") (name "unconnected-(X1O-DATA29-Pad176)") (class "Default")
      (node (ref "X1") (pin "176") (pinfunction "DATA29_176") (pintype "passive"))
    )
    (net (code "181") (name "unconnected-(X1O-DATA31-Pad180)") (class "Default")
      (node (ref "X1") (pin "180") (pinfunction "DATA31_180") (pintype "passive"))
    )
    (net (code "182") (name "unconnected-(X1O-PIN_127{slash}EXT_IO[2]-Pad127)") (class "Default")
      (node (ref "X1") (pin "127") (pinfunction "PIN_127/EXT_IO[2]_127") (pintype "passive"))
    )
    (net (code "183") (name "unconnected-(X1O-PIN_133{slash}EXT_IO[1]-Pad133)") (class "Default")
      (node (ref "X1") (pin "133") (pinfunction "PIN_133/EXT_IO[1]_133") (pintype "passive"))
    )
    (net (code "184") (name "unconnected-(X1O-PIN_135{slash}EXT_IO[0]-Pad135)") (class "Default")
      (node (ref "X1") (pin "135") (pinfunction "PIN_135/EXT_IO[0]_135") (pintype "passive"))
    )
    (net (code "185") (name "unconnected-(X1P-PIN_45-Pad45)") (class "Default")
      (node (ref "X1") (pin "45") (pinfunction "PIN_45_45") (pintype "passive"))
    )
    (net (code "186") (name "unconnected-(X1P-PIN_100-Pad100)") (class "Default")
      (node (ref "X1") (pin "100") (pinfunction "PIN_100_100") (pintype "passive"))
    )
    (net (code "187") (name "unconnected-(X1P-PIN_102-Pad102)") (class "Default")
      (node (ref "X1") (pin "102") (pinfunction "PIN_102_102") (pintype "passive"))
    )
    (net (code "188") (name "unconnected-(X1P-PIN_104-Pad104)") (class "Default")
      (node (ref "X1") (pin "104") (pinfunction "PIN_104_104") (pintype "passive"))
    )
  )
)
